# armBandHeaderShield.net
KiCad netlist of a schematic drawn in EAGLE
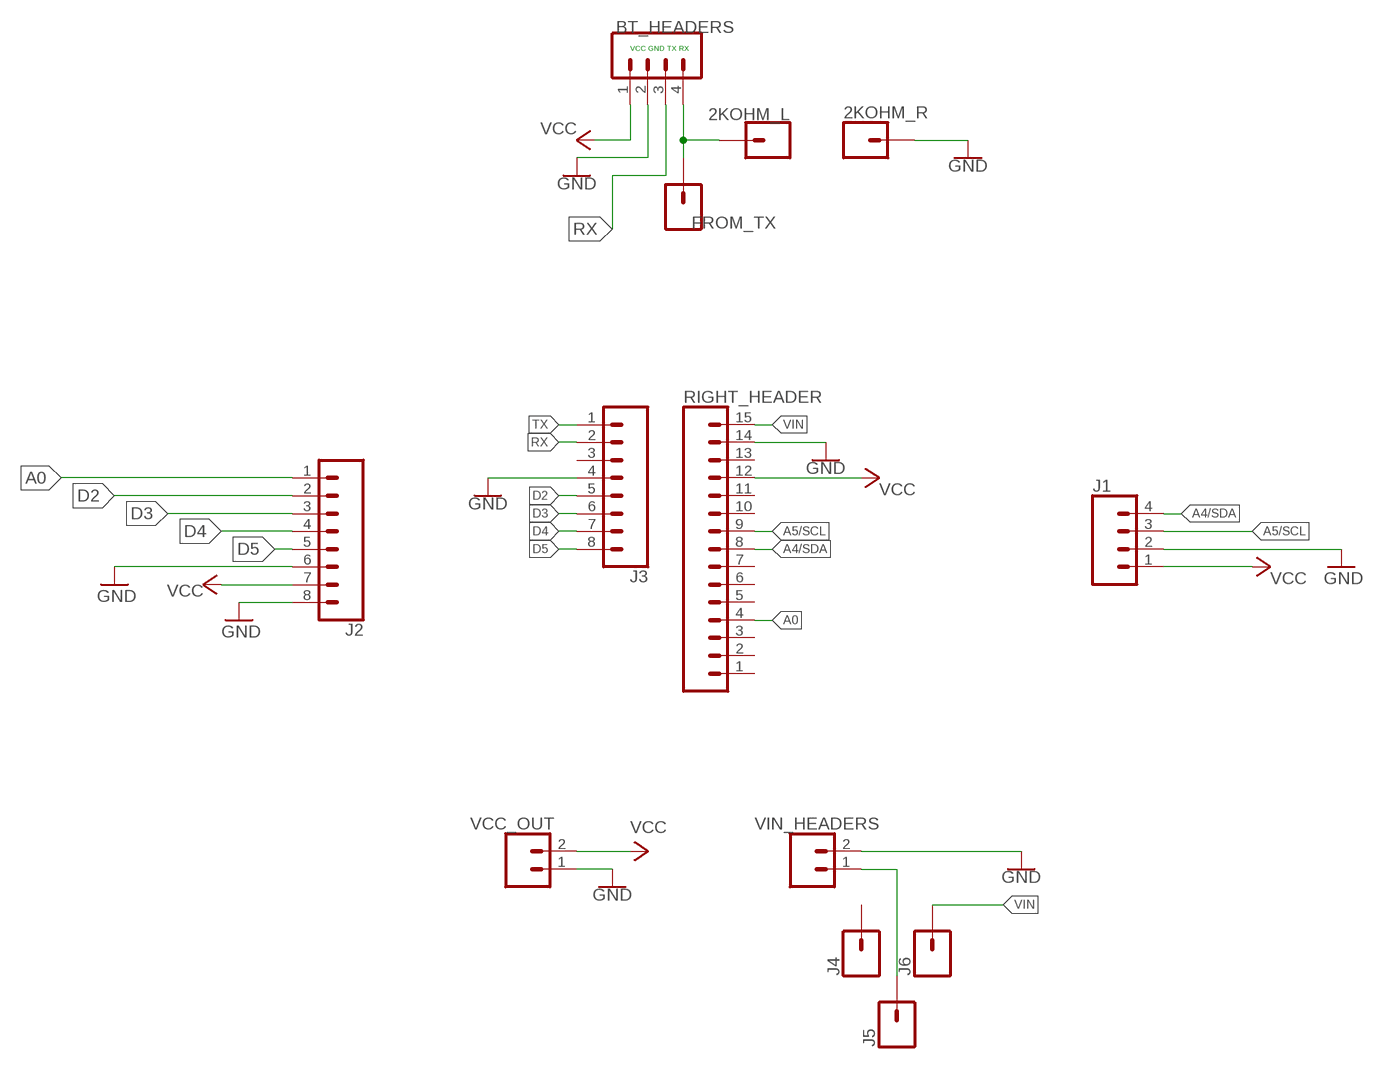
[diagram p0: schematic, sheet 1]

(export (version "E")
  (design (tool "Eeschema 10.0.6"))
  (components
    (comp (ref "2KOHM_L")
      (value "CONN_01")
      (footprint "eagle-import:1X01")
      (libsource (lib "eagle-import") (part "CONN_01"))
    )
    (comp (ref "2KOHM_R")
      (value "CONN_01")
      (footprint "eagle-import:1X01")
      (libsource (lib "eagle-import") (part "CONN_01"))
    )
    (comp (ref "BT_HEADERS")
      (value "CONN_04")
      (footprint "eagle-import:1X04")
      (libsource (lib "eagle-import") (part "CONN_04"))
    )
    (comp (ref "FROM_TX")
      (value "CONN_01")
      (footprint "eagle-import:1X01")
      (libsource (lib "eagle-import") (part "CONN_01"))
    )
    (comp (ref "J1")
      (value "CONN_04")
      (footprint "eagle-import:1X04")
      (libsource (lib "eagle-import") (part "CONN_04"))
    )
    (comp (ref "J2")
      (value "CONN_08\"")
      (footprint "eagle-import:1X08")
      (libsource (lib "eagle-import") (part "CONN_08{dblquote}"))
    )
    (comp (ref "J3")
      (value "CONN_08\"")
      (footprint "eagle-import:1X08")
      (libsource (lib "eagle-import") (part "CONN_08{dblquote}"))
    )
    (comp (ref "J4")
      (value "CONN_01")
      (footprint "eagle-import:1X01")
      (libsource (lib "eagle-import") (part "CONN_01"))
    )
    (comp (ref "J5")
      (value "CONN_01")
      (footprint "eagle-import:1X01")
      (libsource (lib "eagle-import") (part "CONN_01"))
    )
    (comp (ref "J6")
      (value "CONN_01")
      (footprint "eagle-import:1X01")
      (libsource (lib "eagle-import") (part "CONN_01"))
    )
    (comp (ref "RIGHT_HEADER")
      (value "CONN_15")
      (footprint "eagle-import:1X15")
      (libsource (lib "eagle-import") (part "CONN_15"))
    )
    (comp (ref "VCC_OUT")
      (value "CONN_02PTH3")
      (footprint "eagle-import:1X02_LONGPADS")
      (libsource (lib "eagle-import") (part "CONN_02PTH3"))
    )
    (comp (ref "VIN_HEADERS")
      (value "CONN_02PTH3")
      (footprint "eagle-import:1X02_LONGPADS")
      (libsource (lib "eagle-import") (part "CONN_02PTH3"))
    )
  )
  (nets
    (net (code "1") (name "A0") (class "Default")
      (node (ref "J2") (pin "1") (pinfunction "1_1") (pintype "passive"))
      (node (ref "RIGHT_HEADER") (pin "4") (pinfunction "4_4") (pintype "passive"))
    )
    (net (code "2") (name "A4{slash}SDA") (class "Default")
      (node (ref "J1") (pin "4") (pinfunction "4_4") (pintype "passive"))
      (node (ref "RIGHT_HEADER") (pin "8") (pinfunction "8_8") (pintype "passive"))
    )
    (net (code "3") (name "A5{slash}SCL") (class "Default")
      (node (ref "J1") (pin "3") (pinfunction "3_3") (pintype "passive"))
      (node (ref "RIGHT_HEADER") (pin "9") (pinfunction "9_9") (pintype "passive"))
    )
    (net (code "4") (name "D2") (class "Default")
      (node (ref "J2") (pin "2") (pinfunction "2_2") (pintype "passive"))
      (node (ref "J3") (pin "5") (pinfunction "5_5") (pintype "passive"))
    )
    (net (code "5") (name "D3") (class "Default")
      (node (ref "J2") (pin "3") (pinfunction "3_3") (pintype "passive"))
      (node (ref "J3") (pin "6") (pinfunction "6_6") (pintype "passive"))
    )
    (net (code "6") (name "D4") (class "Default")
      (node (ref "J2") (pin "4") (pinfunction "4_4") (pintype "passive"))
      (node (ref "J3") (pin "7") (pinfunction "7_7") (pintype "passive"))
    )
    (net (code "7") (name "D5") (class "Default")
      (node (ref "J2") (pin "5") (pinfunction "5_5") (pintype "passive"))
      (node (ref "J3") (pin "8") (pinfunction "8_8") (pintype "passive"))
    )
    (net (code "8") (name "GND") (class "Default")
      (node (ref "2KOHM_R") (pin "1") (pinfunction "1_1") (pintype "passive"))
      (node (ref "BT_HEADERS") (pin "2") (pinfunction "2_2") (pintype "passive"))
      (node (ref "J1") (pin "2") (pinfunction "2_2") (pintype "passive"))
      (node (ref "J2") (pin "6") (pinfunction "6_6") (pintype "passive"))
      (node (ref "J2") (pin "8") (pinfunction "8_8") (pintype "passive"))
      (node (ref "J3") (pin "4") (pinfunction "4_4") (pintype "passive"))
      (node (ref "RIGHT_HEADER") (pin "14") (pinfunction "14_14") (pintype "passive"))
      (node (ref "VCC_OUT") (pin "1") (pinfunction "1_1") (pintype "passive"))
      (node (ref "VIN_HEADERS") (pin "2") (pinfunction "2_2") (pintype "passive"))
    )
    (net (code "9") (name "Net-(2KOHM_L-Pad1)") (class "Default")
      (node (ref "2KOHM_L") (pin "1") (pinfunction "1_1") (pintype "passive"))
      (node (ref "BT_HEADERS") (pin "4") (pinfunction "4_4") (pintype "passive"))
      (node (ref "FROM_TX") (pin "1") (pinfunction "1_1") (pintype "passive"))
    )
    (net (code "10") (name "Net-(J5-Pad1)") (class "Default")
      (node (ref "J5") (pin "1") (pinfunction "1_1") (pintype "passive"))
      (node (ref "VIN_HEADERS") (pin "1") (pinfunction "1_1") (pintype "passive"))
    )
    (net (code "11") (name "RX") (class "Default")
      (node (ref "BT_HEADERS") (pin "3") (pinfunction "3_3") (pintype "passive"))
      (node (ref "J3") (pin "2") (pinfunction "2_2") (pintype "passive"))
    )
    (net (code "12") (name "TX") (class "Default")
      (node (ref "J3") (pin "1") (pinfunction "1_1") (pintype "passive"))
    )
    (net (code "13") (name "VCC") (class "Default")
      (node (ref "BT_HEADERS") (pin "1") (pinfunction "1_1") (pintype "passive"))
      (node (ref "J1") (pin "1") (pinfunction "1_1") (pintype "passive"))
      (node (ref "J2") (pin "7") (pinfunction "7_7") (pintype "passive"))
      (node (ref "RIGHT_HEADER") (pin "12") (pinfunction "12_12") (pintype "passive"))
      (node (ref "VCC_OUT") (pin "2") (pinfunction "2_2") (pintype "passive"))
    )
    (net (code "14") (name "VIN") (class "Default")
      (node (ref "J6") (pin "1") (pinfunction "1_1") (pintype "passive"))
      (node (ref "RIGHT_HEADER") (pin "15") (pinfunction "15_15") (pintype "passive"))
    )
    (net (code "15") (name "unconnected-(J3-Pad3)") (class "Default")
      (node (ref "J3") (pin "3") (pinfunction "3_3") (pintype "passive"))
    )
    (net (code "16") (name "unconnected-(J4-Pad1)") (class "Default")
      (node (ref "J4") (pin "1") (pinfunction "1_1") (pintype "passive"))
    )
    (net (code "17") (name "unconnected-(RIGHT_HEADER-Pad1)") (class "Default")
      (node (ref "RIGHT_HEADER") (pin "1") (pinfunction "1_1") (pintype "passive"))
    )
    (net (code "18") (name "unconnected-(RIGHT_HEADER-Pad2)") (class "Default")
      (node (ref "RIGHT_HEADER") (pin "2") (pinfunction "2_2") (pintype "passive"))
    )
    (net (code "19") (name "unconnected-(RIGHT_HEADER-Pad3)") (class "Default")
      (node (ref "RIGHT_HEADER") (pin "3") (pinfunction "3_3") (pintype "passive"))
    )
    (net (code "20") (name "unconnected-(RIGHT_HEADER-Pad5)") (class "Default")
      (node (ref "RIGHT_HEADER") (pin "5") (pinfunction "5_5") (pintype "passive"))
    )
    (net (code "21") (name "unconnected-(RIGHT_HEADER-Pad6)") (class "Default")
      (node (ref "RIGHT_HEADER") (pin "6") (pinfunction "6_6") (pintype "passive"))
    )
    (net (code "22") (name "unconnected-(RIGHT_HEADER-Pad7)") (class "Default")
      (node (ref "RIGHT_HEADER") (pin "7") (pinfunction "7_7") (pintype "passive"))
    )
    (net (code "23") (name "unconnected-(RIGHT_HEADER-Pad10)") (class "Default")
      (node (ref "RIGHT_HEADER") (pin "10") (pinfunction "10_10") (pintype "passive"))
    )
    (net (code "24") (name "unconnected-(RIGHT_HEADER-Pad11)") (class "Default")
      (node (ref "RIGHT_HEADER") (pin "11") (pinfunction "11_11") (pintype "passive"))
    )
    (net (code "25") (name "unconnected-(RIGHT_HEADER-Pad13)") (class "Default")
      (node (ref "RIGHT_HEADER") (pin "13") (pinfunction "13_13") (pintype "passive"))
    )
  )
)
